# deploy_sch.net
KiCad netlist of a schematic drawn in EAGLE
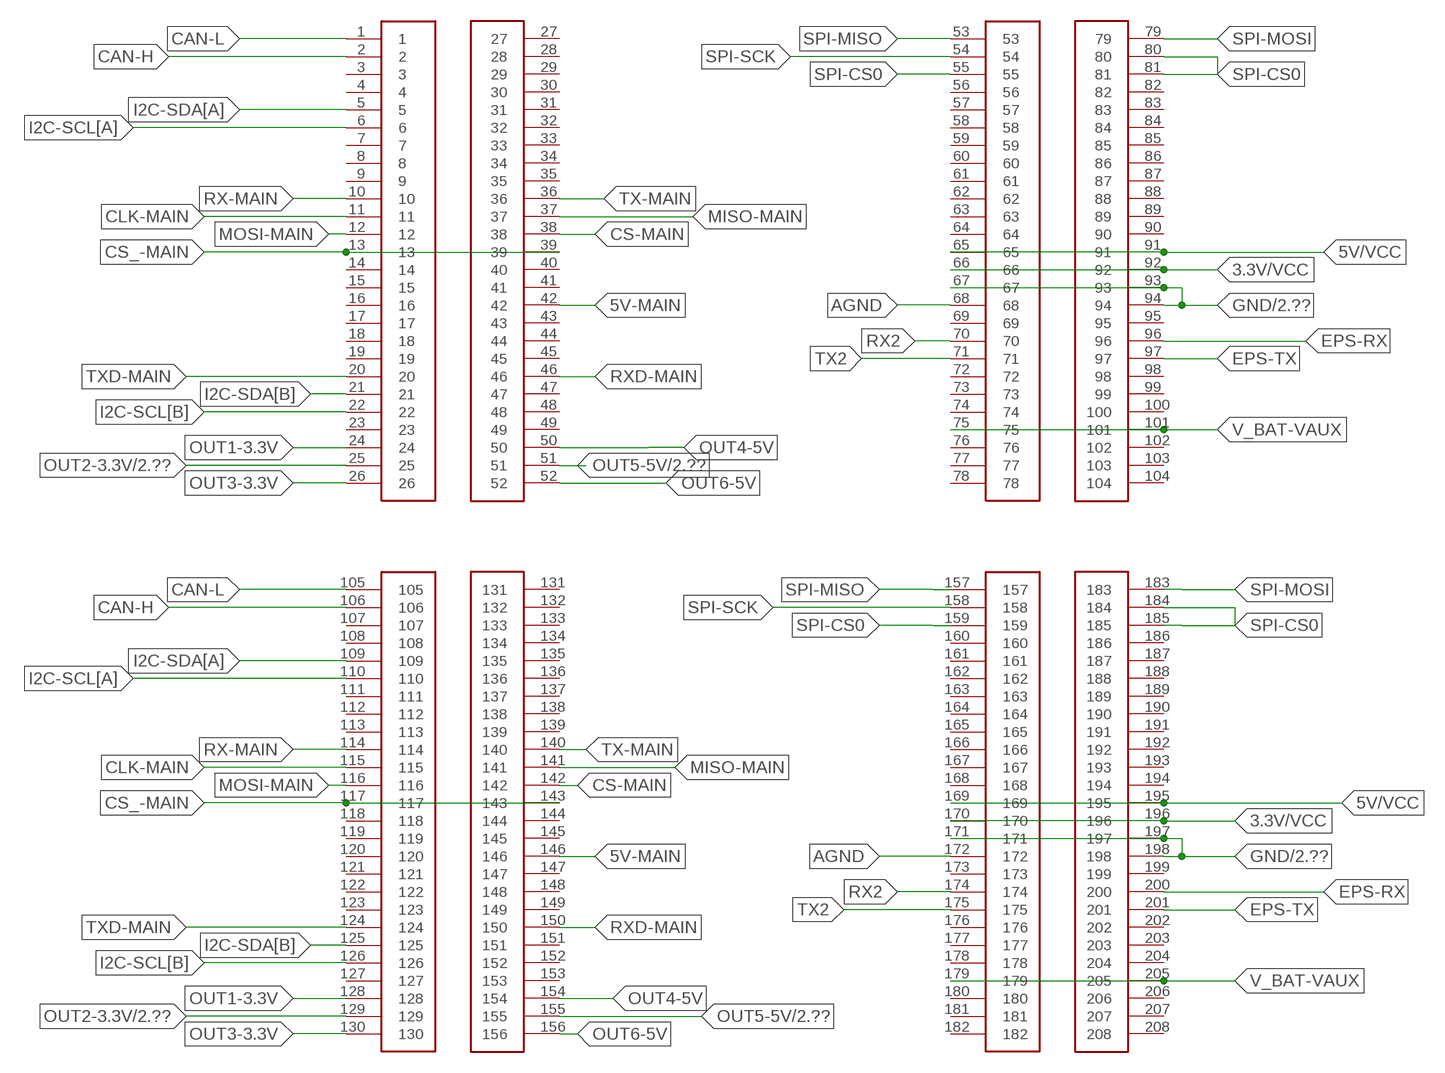
[diagram p0: schematic, sheet 1]
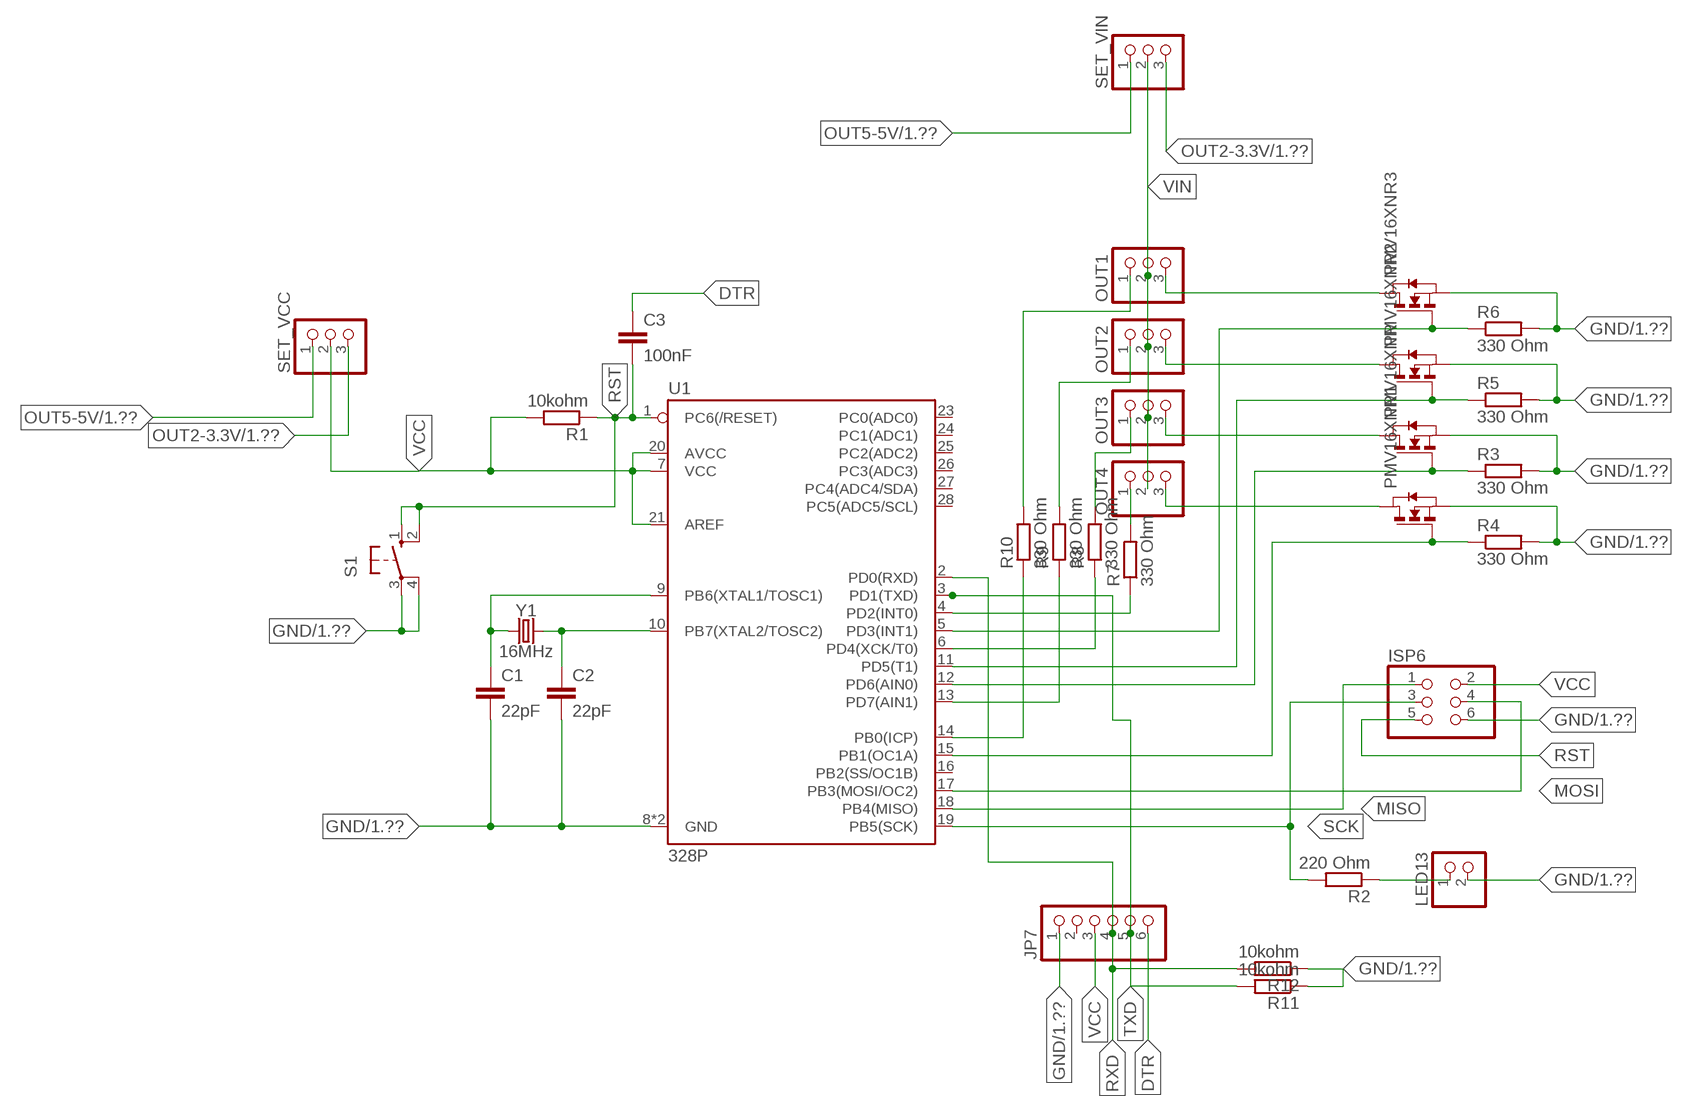
[diagram p1: schematic, sheet 2]

(export (version "E")
  (design (tool "Eeschema 10.0.6"))
  (components
    (comp (ref "C1")
      (value "22pF")
      (footprint "eagle-import:C025-025X050")
      (libsource (lib "eagle-import") (part "C-EU025-025X050"))
    )
    (comp (ref "C2")
      (value "22pF")
      (footprint "eagle-import:C025-025X050")
      (libsource (lib "eagle-import") (part "C-EU025-025X050"))
    )
    (comp (ref "C3")
      (value "100nF")
      (footprint "eagle-import:C025-025X050")
      (libsource (lib "eagle-import") (part "C-EU025-025X050"))
    )
    (comp (ref "ISP6")
      (value "PINHD-2X3")
      (footprint "eagle-import:2X03")
      (libsource (lib "eagle-import") (part "PINHD-2X3"))
    )
    (comp (ref "JP7")
      (value "PINHD-1X6")
      (footprint "eagle-import:1X06")
      (libsource (lib "eagle-import") (part "PINHD-1X6"))
    )
    (comp (ref "LED13")
      (value "PINHD-1X2")
      (footprint "eagle-import:1X02")
      (libsource (lib "eagle-import") (part "PINHD-1X2"))
    )
    (comp (ref "OUT1")
      (value "PINHD-1X3")
      (footprint "eagle-import:1X03")
      (libsource (lib "eagle-import") (part "PINHD-1X3"))
    )
    (comp (ref "OUT2")
      (value "PINHD-1X3")
      (footprint "eagle-import:1X03")
      (libsource (lib "eagle-import") (part "PINHD-1X3"))
    )
    (comp (ref "OUT3")
      (value "PINHD-1X3")
      (footprint "eagle-import:1X03")
      (libsource (lib "eagle-import") (part "PINHD-1X3"))
    )
    (comp (ref "OUT4")
      (value "PINHD-1X3")
      (footprint "eagle-import:1X03")
      (libsource (lib "eagle-import") (part "PINHD-1X3"))
    )
    (comp (ref "PMV16XNR")
      (value "NMOSSOT23")
      (footprint "eagle-import:SOT-23")
      (libsource (lib "eagle-import") (part "NMOSSOT23"))
    )
    (comp (ref "PMV16XNR1")
      (value "NMOSSOT23")
      (footprint "eagle-import:SOT-23")
      (libsource (lib "eagle-import") (part "NMOSSOT23"))
    )
    (comp (ref "PMV16XNR2")
      (value "NMOSSOT23")
      (footprint "eagle-import:SOT-23")
      (libsource (lib "eagle-import") (part "NMOSSOT23"))
    )
    (comp (ref "PMV16XNR3")
      (value "NMOSSOT23")
      (footprint "eagle-import:SOT-23")
      (libsource (lib "eagle-import") (part "NMOSSOT23"))
    )
    (comp (ref "R1")
      (value "10kohm")
      (footprint "eagle-import:0204_7")
      (libsource (lib "eagle-import") (part "R-EU_0204/7"))
    )
    (comp (ref "R2")
      (value "220 Ohm")
      (footprint "eagle-import:0204_7")
      (libsource (lib "eagle-import") (part "R-EU_0204/7"))
    )
    (comp (ref "R3")
      (value "330 Ohm")
      (footprint "eagle-import:0204_7")
      (libsource (lib "eagle-import") (part "R-EU_0204/7"))
    )
    (comp (ref "R4")
      (value "330 Ohm")
      (footprint "eagle-import:0204_7")
      (libsource (lib "eagle-import") (part "R-EU_0204/7"))
    )
    (comp (ref "R5")
      (value "330 Ohm")
      (footprint "eagle-import:0204_7")
      (libsource (lib "eagle-import") (part "R-EU_0204/7"))
    )
    (comp (ref "R6")
      (value "330 Ohm")
      (footprint "eagle-import:0204_7")
      (libsource (lib "eagle-import") (part "R-EU_0204/7"))
    )
    (comp (ref "R7")
      (value "330 Ohm")
      (footprint "eagle-import:0204_7")
      (libsource (lib "eagle-import") (part "R-EU_0204/7"))
    )
    (comp (ref "R8")
      (value "330 Ohm")
      (footprint "eagle-import:0204_7")
      (libsource (lib "eagle-import") (part "R-EU_0204/7"))
    )
    (comp (ref "R9")
      (value "330 Ohm")
      (footprint "eagle-import:0204_7")
      (libsource (lib "eagle-import") (part "R-EU_0204/7"))
    )
    (comp (ref "R10")
      (value "330 Ohm")
      (footprint "eagle-import:0204_7")
      (libsource (lib "eagle-import") (part "R-EU_0204/7"))
    )
    (comp (ref "R11")
      (value "10kohm")
      (footprint "eagle-import:0204_7")
      (libsource (lib "eagle-import") (part "R-EU_0204/7"))
    )
    (comp (ref "R12")
      (value "10kohm")
      (footprint "eagle-import:0204_7")
      (libsource (lib "eagle-import") (part "R-EU_0204/7"))
    )
    (comp (ref "S1")
      (value "10-XX")
      (footprint "eagle-import:B3F-10XX")
      (fields (field (name "MPN") "B3F-1000"))
      (libsource (lib "eagle-import") (part "10-XX"))
    )
    (comp (ref "SET_VCC")
      (value "PINHD-1X3")
      (footprint "eagle-import:1X03")
      (libsource (lib "eagle-import") (part "PINHD-1X3"))
    )
    (comp (ref "SET_VIN")
      (value "PINHD-1X3")
      (footprint "eagle-import:1X03")
      (libsource (lib "eagle-import") (part "PINHD-1X3"))
    )
    (comp (ref "U1")
      (value "328P")
      (footprint "eagle-import:DIP28")
      (libsource (lib "eagle-import") (part "ATMEGA328P_PDIP"))
    )
    (comp (ref "Y1")
      (value "16MHz")
      (footprint "eagle-import:HC49US")
      (libsource (lib "eagle-import") (part "CRYSTAL-16MHZPTH-HC49US"))
    )
    (comp (ref "U$1")
      (value "SUCHAI_STACKBREAKOUT")
      (footprint "eagle-import:SUCHAI_STACKBREAKOUT")
      (libsource (lib "eagle-import") (part "SUCHAI_STACKBREAKOUT"))
    )
  )
  (nets
    (net (code "1") (name "3.3V{slash}VCC") (class "Default")
      (node (ref "U$1") (pin "170") (pinfunction "170_170") (pintype "bidirectional"))
      (node (ref "U$1") (pin "196") (pinfunction "196_196") (pintype "bidirectional"))
      (node (ref "U$1") (pin "66") (pinfunction "66_66") (pintype "bidirectional"))
      (node (ref "U$1") (pin "92") (pinfunction "92_92") (pintype "bidirectional"))
    )
    (net (code "2") (name "5V-MAIN") (class "Default")
      (node (ref "U$1") (pin "146") (pinfunction "146_146") (pintype "bidirectional"))
      (node (ref "U$1") (pin "42") (pinfunction "42_42") (pintype "bidirectional"))
    )
    (net (code "3") (name "5V{slash}VCC") (class "Default")
      (node (ref "U$1") (pin "169") (pinfunction "169_169") (pintype "bidirectional"))
      (node (ref "U$1") (pin "195") (pinfunction "195_195") (pintype "bidirectional"))
      (node (ref "U$1") (pin "65") (pinfunction "65_65") (pintype "bidirectional"))
      (node (ref "U$1") (pin "91") (pinfunction "91_91") (pintype "bidirectional"))
    )
    (net (code "4") (name "AGND") (class "Default")
      (node (ref "U$1") (pin "172") (pinfunction "172_172") (pintype "bidirectional"))
      (node (ref "U$1") (pin "68") (pinfunction "68_68") (pintype "bidirectional"))
    )
    (net (code "5") (name "CAN-H") (class "Default")
      (node (ref "U$1") (pin "106") (pinfunction "106_106") (pintype "bidirectional"))
      (node (ref "U$1") (pin "2") (pinfunction "2_2") (pintype "bidirectional"))
    )
    (net (code "6") (name "CAN-L") (class "Default")
      (node (ref "U$1") (pin "1") (pinfunction "1_1") (pintype "bidirectional"))
      (node (ref "U$1") (pin "105") (pinfunction "105_105") (pintype "bidirectional"))
    )
    (net (code "7") (name "CLK-MAIN") (class "Default")
      (node (ref "U$1") (pin "11") (pinfunction "11_11") (pintype "bidirectional"))
      (node (ref "U$1") (pin "115") (pinfunction "115_115") (pintype "bidirectional"))
    )
    (net (code "8") (name "CS-MAIN") (class "Default")
      (node (ref "U$1") (pin "142") (pinfunction "142_142") (pintype "bidirectional"))
      (node (ref "U$1") (pin "38") (pinfunction "38_38") (pintype "bidirectional"))
    )
    (net (code "9") (name "CS_-MAIN") (class "Default")
      (node (ref "U$1") (pin "117") (pinfunction "117_117") (pintype "bidirectional"))
      (node (ref "U$1") (pin "13") (pinfunction "13_13") (pintype "bidirectional"))
      (node (ref "U$1") (pin "143") (pinfunction "143_143") (pintype "bidirectional"))
      (node (ref "U$1") (pin "39") (pinfunction "39_39") (pintype "bidirectional"))
    )
    (net (code "10") (name "DTR") (class "Default")
      (node (ref "C3") (pin "1") (pinfunction "1_1") (pintype "passive"))
      (node (ref "JP7") (pin "6") (pinfunction "6_6") (pintype "passive"))
    )
    (net (code "11") (name "EPS-RX") (class "Default")
      (node (ref "U$1") (pin "200") (pinfunction "200_200") (pintype "bidirectional"))
      (node (ref "U$1") (pin "96") (pinfunction "96_96") (pintype "bidirectional"))
    )
    (net (code "12") (name "EPS-TX") (class "Default")
      (node (ref "U$1") (pin "201") (pinfunction "201_201") (pintype "bidirectional"))
      (node (ref "U$1") (pin "97") (pinfunction "97_97") (pintype "bidirectional"))
    )
    (net (code "13") (name "GND") (class "Default")
      (node (ref "C1") (pin "2") (pinfunction "2_2") (pintype "passive"))
      (node (ref "C2") (pin "2") (pinfunction "2_2") (pintype "passive"))
      (node (ref "ISP6") (pin "6") (pinfunction "6_6") (pintype "passive"))
      (node (ref "JP7") (pin "1") (pinfunction "1_1") (pintype "passive"))
      (node (ref "LED13") (pin "2") (pinfunction "2_2") (pintype "passive"))
      (node (ref "PMV16XNR") (pin "2") (pinfunction "S_2") (pintype "passive"))
      (node (ref "PMV16XNR1") (pin "2") (pinfunction "S_2") (pintype "passive"))
      (node (ref "PMV16XNR2") (pin "2") (pinfunction "S_2") (pintype "passive"))
      (node (ref "PMV16XNR3") (pin "2") (pinfunction "S_2") (pintype "passive"))
      (node (ref "R11") (pin "1") (pinfunction "1_1") (pintype "passive"))
      (node (ref "R12") (pin "1") (pinfunction "1_1") (pintype "passive"))
      (node (ref "R3") (pin "2") (pinfunction "2_2") (pintype "passive"))
      (node (ref "R4") (pin "2") (pinfunction "2_2") (pintype "passive"))
      (node (ref "R5") (pin "2") (pinfunction "2_2") (pintype "passive"))
      (node (ref "R6") (pin "2") (pinfunction "2_2") (pintype "passive"))
      (node (ref "S1") (pin "3") (pinfunction "P_3") (pintype "passive"))
      (node (ref "S1") (pin "4") (pinfunction "P1_4") (pintype "passive"))
      (node (ref "U$1") (pin "171") (pinfunction "171_171") (pintype "bidirectional"))
      (node (ref "U$1") (pin "197") (pinfunction "197_197") (pintype "bidirectional"))
      (node (ref "U$1") (pin "198") (pinfunction "198_198") (pintype "bidirectional"))
      (node (ref "U$1") (pin "67") (pinfunction "67_67") (pintype "bidirectional"))
      (node (ref "U$1") (pin "93") (pinfunction "93_93") (pintype "bidirectional"))
      (node (ref "U$1") (pin "94") (pinfunction "94_94") (pintype "bidirectional"))
      (node (ref "U1") (pin "22") (pinfunction "GND_22") (pintype "bidirectional"))
      (node (ref "U1") (pin "8") (pinfunction "GND_8") (pintype "bidirectional"))
    )
    (net (code "14") (name "I2C-SCL[A]") (class "Default")
      (node (ref "U$1") (pin "110") (pinfunction "110_110") (pintype "bidirectional"))
      (node (ref "U$1") (pin "6") (pinfunction "6_6") (pintype "bidirectional"))
    )
    (net (code "15") (name "I2C-SCL[B]") (class "Default")
      (node (ref "U$1") (pin "126") (pinfunction "126_126") (pintype "bidirectional"))
      (node (ref "U$1") (pin "22") (pinfunction "22_22") (pintype "bidirectional"))
    )
    (net (code "16") (name "I2C-SDA[A]") (class "Default")
      (node (ref "U$1") (pin "109") (pinfunction "109_109") (pintype "bidirectional"))
      (node (ref "U$1") (pin "5") (pinfunction "5_5") (pintype "bidirectional"))
    )
    (net (code "17") (name "I2C-SDA[B]") (class "Default")
      (node (ref "U$1") (pin "125") (pinfunction "125_125") (pintype "bidirectional"))
      (node (ref "U$1") (pin "21") (pinfunction "21_21") (pintype "bidirectional"))
    )
    (net (code "18") (name "MISO") (class "Default")
      (node (ref "ISP6") (pin "1") (pinfunction "1_1") (pintype "passive"))
      (node (ref "U1") (pin "18") (pinfunction "PB4(MISO)_18") (pintype "bidirectional"))
    )
    (net (code "19") (name "MISO-MAIN") (class "Default")
      (node (ref "U$1") (pin "141") (pinfunction "141_141") (pintype "bidirectional"))
      (node (ref "U$1") (pin "37") (pinfunction "37_37") (pintype "bidirectional"))
    )
    (net (code "20") (name "MOSI") (class "Default")
      (node (ref "ISP6") (pin "4") (pinfunction "4_4") (pintype "passive"))
      (node (ref "U1") (pin "17") (pinfunction "PB3(MOSI/OC2)_17") (pintype "bidirectional"))
    )
    (net (code "21") (name "MOSI-MAIN") (class "Default")
      (node (ref "U$1") (pin "116") (pinfunction "116_116") (pintype "bidirectional"))
      (node (ref "U$1") (pin "12") (pinfunction "12_12") (pintype "bidirectional"))
    )
    (net (code "22") (name "Net-(LED13-Pad1)") (class "Default")
      (node (ref "LED13") (pin "1") (pinfunction "1_1") (pintype "passive"))
      (node (ref "R2") (pin "1") (pinfunction "1_1") (pintype "passive"))
    )
    (net (code "23") (name "Net-(OUT1-Pad1)") (class "Default")
      (node (ref "OUT1") (pin "1") (pinfunction "1_1") (pintype "passive"))
      (node (ref "R10") (pin "2") (pinfunction "2_2") (pintype "passive"))
    )
    (net (code "24") (name "Net-(OUT2-Pad1)") (class "Default")
      (node (ref "OUT2") (pin "1") (pinfunction "1_1") (pintype "passive"))
      (node (ref "R9") (pin "2") (pinfunction "2_2") (pintype "passive"))
    )
    (net (code "25") (name "Net-(OUT3-Pad1)") (class "Default")
      (node (ref "OUT3") (pin "1") (pinfunction "1_1") (pintype "passive"))
      (node (ref "R8") (pin "2") (pinfunction "2_2") (pintype "passive"))
    )
    (net (code "26") (name "Net-(OUT4-Pad1)") (class "Default")
      (node (ref "OUT4") (pin "1") (pinfunction "1_1") (pintype "passive"))
      (node (ref "R7") (pin "2") (pinfunction "2_2") (pintype "passive"))
    )
    (net (code "27") (name "Net-(PMV16XNR-D)") (class "Default")
      (node (ref "OUT3") (pin "3") (pinfunction "3_3") (pintype "passive"))
      (node (ref "PMV16XNR") (pin "1") (pinfunction "D_1") (pintype "passive"))
    )
    (net (code "28") (name "Net-(PMV16XNR-G)") (class "Default")
      (node (ref "PMV16XNR") (pin "3") (pinfunction "G_3") (pintype "passive"))
      (node (ref "R3") (pin "1") (pinfunction "1_1") (pintype "passive"))
      (node (ref "U1") (pin "12") (pinfunction "PD6(AIN0)_12") (pintype "bidirectional"))
    )
    (net (code "29") (name "Net-(PMV16XNR1-D)") (class "Default")
      (node (ref "OUT4") (pin "3") (pinfunction "3_3") (pintype "passive"))
      (node (ref "PMV16XNR1") (pin "1") (pinfunction "D_1") (pintype "passive"))
    )
    (net (code "30") (name "Net-(PMV16XNR1-G)") (class "Default")
      (node (ref "PMV16XNR1") (pin "3") (pinfunction "G_3") (pintype "passive"))
      (node (ref "R4") (pin "1") (pinfunction "1_1") (pintype "passive"))
      (node (ref "U1") (pin "15") (pinfunction "PB1(OC1A)_15") (pintype "bidirectional"))
    )
    (net (code "31") (name "Net-(PMV16XNR2-D)") (class "Default")
      (node (ref "OUT2") (pin "3") (pinfunction "3_3") (pintype "passive"))
      (node (ref "PMV16XNR2") (pin "1") (pinfunction "D_1") (pintype "passive"))
    )
    (net (code "32") (name "Net-(PMV16XNR2-G)") (class "Default")
      (node (ref "PMV16XNR2") (pin "3") (pinfunction "G_3") (pintype "passive"))
      (node (ref "R5") (pin "1") (pinfunction "1_1") (pintype "passive"))
      (node (ref "U1") (pin "11") (pinfunction "PD5(T1)_11") (pintype "bidirectional"))
    )
    (net (code "33") (name "Net-(PMV16XNR3-D)") (class "Default")
      (node (ref "OUT1") (pin "3") (pinfunction "3_3") (pintype "passive"))
      (node (ref "PMV16XNR3") (pin "1") (pinfunction "D_1") (pintype "passive"))
    )
    (net (code "34") (name "Net-(PMV16XNR3-G)") (class "Default")
      (node (ref "PMV16XNR3") (pin "3") (pinfunction "G_3") (pintype "passive"))
      (node (ref "R6") (pin "1") (pinfunction "1_1") (pintype "passive"))
      (node (ref "U1") (pin "5") (pinfunction "PD3(INT1)_5") (pintype "bidirectional"))
    )
    (net (code "35") (name "Net-(U1-PB0(ICP))") (class "Default")
      (node (ref "R10") (pin "1") (pinfunction "1_1") (pintype "passive"))
      (node (ref "U1") (pin "14") (pinfunction "PB0(ICP)_14") (pintype "bidirectional"))
    )
    (net (code "36") (name "Net-(U1-PB6(XTAL1{slash}TOSC1))") (class "Default")
      (node (ref "C1") (pin "1") (pinfunction "1_1") (pintype "passive"))
      (node (ref "U1") (pin "9") (pinfunction "PB6(XTAL1/TOSC1)_9") (pintype "bidirectional"))
      (node (ref "Y1") (pin "1") (pinfunction "1_1") (pintype "passive"))
    )
    (net (code "37") (name "Net-(U1-PB7(XTAL2{slash}TOSC2))") (class "Default")
      (node (ref "C2") (pin "1") (pinfunction "1_1") (pintype "passive"))
      (node (ref "U1") (pin "10") (pinfunction "PB7(XTAL2/TOSC2)_10") (pintype "bidirectional"))
      (node (ref "Y1") (pin "2") (pinfunction "2_2") (pintype "passive"))
    )
    (net (code "38") (name "Net-(U1-PD2(INT0))") (class "Default")
      (node (ref "R7") (pin "1") (pinfunction "1_1") (pintype "passive"))
      (node (ref "U1") (pin "4") (pinfunction "PD2(INT0)_4") (pintype "bidirectional"))
    )
    (net (code "39") (name "Net-(U1-PD4(XCK{slash}T0))") (class "Default")
      (node (ref "R8") (pin "1") (pinfunction "1_1") (pintype "passive"))
      (node (ref "U1") (pin "6") (pinfunction "PD4(XCK/T0)_6") (pintype "bidirectional"))
    )
    (net (code "40") (name "Net-(U1-PD7(AIN1))") (class "Default")
      (node (ref "R9") (pin "1") (pinfunction "1_1") (pintype "passive"))
      (node (ref "U1") (pin "13") (pinfunction "PD7(AIN1)_13") (pintype "bidirectional"))
    )
    (net (code "41") (name "OUT1-3.3V") (class "Default")
      (node (ref "U$1") (pin "128") (pinfunction "128_128") (pintype "bidirectional"))
      (node (ref "U$1") (pin "24") (pinfunction "24_24") (pintype "bidirectional"))
    )
    (net (code "42") (name "OUT2-3.3V") (class "Default")
      (node (ref "SET_VCC") (pin "3") (pinfunction "3_3") (pintype "passive"))
      (node (ref "SET_VIN") (pin "3") (pinfunction "3_3") (pintype "passive"))
      (node (ref "U$1") (pin "129") (pinfunction "129_129") (pintype "bidirectional"))
      (node (ref "U$1") (pin "25") (pinfunction "25_25") (pintype "bidirectional"))
    )
    (net (code "43") (name "OUT3-3.3V") (class "Default")
      (node (ref "U$1") (pin "130") (pinfunction "130_130") (pintype "bidirectional"))
      (node (ref "U$1") (pin "26") (pinfunction "26_26") (pintype "bidirectional"))
    )
    (net (code "44") (name "OUT4-5V") (class "Default")
      (node (ref "U$1") (pin "154") (pinfunction "154_154") (pintype "bidirectional"))
      (node (ref "U$1") (pin "50") (pinfunction "50_50") (pintype "bidirectional"))
    )
    (net (code "45") (name "OUT5-5V") (class "Default")
      (node (ref "SET_VCC") (pin "1") (pinfunction "1_1") (pintype "passive"))
      (node (ref "SET_VIN") (pin "1") (pinfunction "1_1") (pintype "passive"))
      (node (ref "U$1") (pin "155") (pinfunction "155_155") (pintype "bidirectional"))
      (node (ref "U$1") (pin "51") (pinfunction "51_51") (pintype "bidirectional"))
    )
    (net (code "46") (name "OUT6-5V") (class "Default")
      (node (ref "U$1") (pin "156") (pinfunction "156_156") (pintype "bidirectional"))
      (node (ref "U$1") (pin "52") (pinfunction "52_52") (pintype "bidirectional"))
    )
    (net (code "47") (name "RST") (class "Default")
      (node (ref "C3") (pin "2") (pinfunction "2_2") (pintype "passive"))
      (node (ref "ISP6") (pin "5") (pinfunction "5_5") (pintype "passive"))
      (node (ref "R1") (pin "1") (pinfunction "1_1") (pintype "passive"))
      (node (ref "S1") (pin "1") (pinfunction "S_1") (pintype "passive"))
      (node (ref "S1") (pin "2") (pinfunction "S1_2") (pintype "passive"))
      (node (ref "U1") (pin "1") (pinfunction "PC6(/RESET)_1") (pintype "bidirectional"))
    )
    (net (code "48") (name "RX-MAIN") (class "Default")
      (node (ref "U$1") (pin "10") (pinfunction "10_10") (pintype "bidirectional"))
      (node (ref "U$1") (pin "114") (pinfunction "114_114") (pintype "bidirectional"))
    )
    (net (code "49") (name "RX2") (class "Default")
      (node (ref "U$1") (pin "174") (pinfunction "174_174") (pintype "bidirectional"))
      (node (ref "U$1") (pin "70") (pinfunction "70_70") (pintype "bidirectional"))
    )
    (net (code "50") (name "RXD") (class "Default")
      (node (ref "JP7") (pin "4") (pinfunction "4_4") (pintype "passive"))
      (node (ref "R12") (pin "2") (pinfunction "2_2") (pintype "passive"))
      (node (ref "U1") (pin "2") (pinfunction "PD0(RXD)_2") (pintype "bidirectional"))
    )
    (net (code "51") (name "RXD-MAIN") (class "Default")
      (node (ref "U$1") (pin "150") (pinfunction "150_150") (pintype "bidirectional"))
      (node (ref "U$1") (pin "46") (pinfunction "46_46") (pintype "bidirectional"))
    )
    (net (code "52") (name "SCK") (class "Default")
      (node (ref "ISP6") (pin "3") (pinfunction "3_3") (pintype "passive"))
      (node (ref "R2") (pin "2") (pinfunction "2_2") (pintype "passive"))
      (node (ref "U1") (pin "19") (pinfunction "PB5(SCK)_19") (pintype "bidirectional"))
    )
    (net (code "53") (name "SPI-CS0") (class "Default")
      (node (ref "U$1") (pin "159") (pinfunction "159_159") (pintype "bidirectional"))
      (node (ref "U$1") (pin "184") (pinfunction "184_184") (pintype "bidirectional"))
      (node (ref "U$1") (pin "185") (pinfunction "185_185") (pintype "bidirectional"))
      (node (ref "U$1") (pin "55") (pinfunction "55_55") (pintype "bidirectional"))
      (node (ref "U$1") (pin "80") (pinfunction "80_80") (pintype "bidirectional"))
      (node (ref "U$1") (pin "81") (pinfunction "81_81") (pintype "bidirectional"))
    )
    (net (code "54") (name "SPI-MISO") (class "Default")
      (node (ref "U$1") (pin "157") (pinfunction "157_157") (pintype "bidirectional"))
      (node (ref "U$1") (pin "53") (pinfunction "53_53") (pintype "bidirectional"))
    )
    (net (code "55") (name "SPI-MOSI") (class "Default")
      (node (ref "U$1") (pin "183") (pinfunction "183_183") (pintype "bidirectional"))
      (node (ref "U$1") (pin "79") (pinfunction "79_79") (pintype "bidirectional"))
    )
    (net (code "56") (name "SPI-SCK") (class "Default")
      (node (ref "U$1") (pin "158") (pinfunction "158_158") (pintype "bidirectional"))
      (node (ref "U$1") (pin "54") (pinfunction "54_54") (pintype "bidirectional"))
    )
    (net (code "57") (name "TX-MAIN") (class "Default")
      (node (ref "U$1") (pin "140") (pinfunction "140_140") (pintype "bidirectional"))
      (node (ref "U$1") (pin "36") (pinfunction "36_36") (pintype "bidirectional"))
    )
    (net (code "58") (name "TX2") (class "Default")
      (node (ref "U$1") (pin "175") (pinfunction "175_175") (pintype "bidirectional"))
      (node (ref "U$1") (pin "71") (pinfunction "71_71") (pintype "bidirectional"))
    )
    (net (code "59") (name "TXD") (class "Default")
      (node (ref "JP7") (pin "5") (pinfunction "5_5") (pintype "passive"))
      (node (ref "R11") (pin "2") (pinfunction "2_2") (pintype "passive"))
      (node (ref "U1") (pin "3") (pinfunction "PD1(TXD)_3") (pintype "bidirectional"))
    )
    (net (code "60") (name "TXD-MAIN") (class "Default")
      (node (ref "U$1") (pin "124") (pinfunction "124_124") (pintype "bidirectional"))
      (node (ref "U$1") (pin "20") (pinfunction "20_20") (pintype "bidirectional"))
    )
    (net (code "61") (name "VCC") (class "Default")
      (node (ref "ISP6") (pin "2") (pinfunction "2_2") (pintype "passive"))
      (node (ref "JP7") (pin "3") (pinfunction "3_3") (pintype "passive"))
      (node (ref "R1") (pin "2") (pinfunction "2_2") (pintype "passive"))
      (node (ref "SET_VCC") (pin "2") (pinfunction "2_2") (pintype "passive"))
      (node (ref "U1") (pin "20") (pinfunction "AVCC_20") (pintype "bidirectional"))
      (node (ref "U1") (pin "21") (pinfunction "AREF_21") (pintype "bidirectional"))
      (node (ref "U1") (pin "7") (pinfunction "VCC_7") (pintype "bidirectional"))
    )
    (net (code "62") (name "VIN") (class "Default")
      (node (ref "OUT1") (pin "2") (pinfunction "2_2") (pintype "passive"))
      (node (ref "OUT2") (pin "2") (pinfunction "2_2") (pintype "passive"))
      (node (ref "OUT3") (pin "2") (pinfunction "2_2") (pintype "passive"))
      (node (ref "OUT4") (pin "2") (pinfunction "2_2") (pintype "passive"))
      (node (ref "SET_VIN") (pin "2") (pinfunction "2_2") (pintype "passive"))
    )
    (net (code "63") (name "V_BAT-VAUX") (class "Default")
      (node (ref "U$1") (pin "101") (pinfunction "101_101") (pintype "bidirectional"))
      (node (ref "U$1") (pin "179") (pinfunction "179_179") (pintype "bidirectional"))
      (node (ref "U$1") (pin "205") (pinfunction "205_205") (pintype "bidirectional"))
      (node (ref "U$1") (pin "75") (pinfunction "75_75") (pintype "bidirectional"))
    )
    (net (code "64") (name "unconnected-(JP7-Pad2)") (class "Default")
      (node (ref "JP7") (pin "2") (pinfunction "2_2") (pintype "passive"))
    )
    (net (code "65") (name "unconnected-(U$1-Pad3)") (class "Default")
      (node (ref "U$1") (pin "3") (pinfunction "3_3") (pintype "bidirectional"))
    )
    (net (code "66") (name "unconnected-(U$1-Pad4)") (class "Default")
      (node (ref "U$1") (pin "4") (pinfunction "4_4") (pintype "bidirectional"))
    )
    (net (code "67") (name "unconnected-(U$1-Pad7)") (class "Default")
      (node (ref "U$1") (pin "7") (pinfunction "7_7") (pintype "bidirectional"))
    )
    (net (code "68") (name "unconnected-(U$1-Pad8)") (class "Default")
      (node (ref "U$1") (pin "8") (pinfunction "8_8") (pintype "bidirectional"))
    )
    (net (code "69") (name "unconnected-(U$1-Pad9)") (class "Default")
      (node (ref "U$1") (pin "9") (pinfunction "9_9") (pintype "bidirectional"))
    )
    (net (code "70") (name "unconnected-(U$1-Pad14)") (class "Default")
      (node (ref "U$1") (pin "14") (pinfunction "14_14") (pintype "bidirectional"))
    )
    (net (code "71") (name "unconnected-(U$1-Pad15)") (class "Default")
      (node (ref "U$1") (pin "15") (pinfunction "15_15") (pintype "bidirectional"))
    )
    (net (code "72") (name "unconnected-(U$1-Pad16)") (class "Default")
      (node (ref "U$1") (pin "16") (pinfunction "16_16") (pintype "bidirectional"))
    )
    (net (code "73") (name "unconnected-(U$1-Pad17)") (class "Default")
      (node (ref "U$1") (pin "17") (pinfunction "17_17") (pintype "bidirectional"))
    )
    (net (code "74") (name "unconnected-(U$1-Pad18)") (class "Default")
      (node (ref "U$1") (pin "18") (pinfunction "18_18") (pintype "bidirectional"))
    )
    (net (code "75") (name "unconnected-(U$1-Pad19)") (class "Default")
      (node (ref "U$1") (pin "19") (pinfunction "19_19") (pintype "bidirectional"))
    )
    (net (code "76") (name "unconnected-(U$1-Pad23)") (class "Default")
      (node (ref "U$1") (pin "23") (pinfunction "23_23") (pintype "bidirectional"))
    )
    (net (code "77") (name "unconnected-(U$1-Pad27)") (class "Default")
      (node (ref "U$1") (pin "27") (pinfunction "27_27") (pintype "bidirectional"))
    )
    (net (code "78") (name "unconnected-(U$1-Pad28)") (class "Default")
      (node (ref "U$1") (pin "28") (pinfunction "28_28") (pintype "bidirectional"))
    )
    (net (code "79") (name "unconnected-(U$1-Pad29)") (class "Default")
      (node (ref "U$1") (pin "29") (pinfunction "29_29") (pintype "bidirectional"))
    )
    (net (code "80") (name "unconnected-(U$1-Pad30)") (class "Default")
      (node (ref "U$1") (pin "30") (pinfunction "30_30") (pintype "bidirectional"))
    )
    (net (code "81") (name "unconnected-(U$1-Pad31)") (class "Default")
      (node (ref "U$1") (pin "31") (pinfunction "31_31") (pintype "bidirectional"))
    )
    (net (code "82") (name "unconnected-(U$1-Pad32)") (class "Default")
      (node (ref "U$1") (pin "32") (pinfunction "32_32") (pintype "bidirectional"))
    )
    (net (code "83") (name "unconnected-(U$1-Pad33)") (class "Default")
      (node (ref "U$1") (pin "33") (pinfunction "33_33") (pintype "bidirectional"))
    )
    (net (code "84") (name "unconnected-(U$1-Pad34)") (class "Default")
      (node (ref "U$1") (pin "34") (pinfunction "34_34") (pintype "bidirectional"))
    )
    (net (code "85") (name "unconnected-(U$1-Pad35)") (class "Default")
      (node (ref "U$1") (pin "35") (pinfunction "35_35") (pintype "bidirectional"))
    )
    (net (code "86") (name "unconnected-(U$1-Pad40)") (class "Default")
      (node (ref "U$1") (pin "40") (pinfunction "40_40") (pintype "bidirectional"))
    )
    (net (code "87") (name "unconnected-(U$1-Pad41)") (class "Default")
      (node (ref "U$1") (pin "41") (pinfunction "41_41") (pintype "bidirectional"))
    )
    (net (code "88") (name "unconnected-(U$1-Pad43)") (class "Default")
      (node (ref "U$1") (pin "43") (pinfunction "43_43") (pintype "bidirectional"))
    )
    (net (code "89") (name "unconnected-(U$1-Pad44)") (class "Default")
      (node (ref "U$1") (pin "44") (pinfunction "44_44") (pintype "bidirectional"))
    )
    (net (code "90") (name "unconnected-(U$1-Pad45)") (class "Default")
      (node (ref "U$1") (pin "45") (pinfunction "45_45") (pintype "bidirectional"))
    )
    (net (code "91") (name "unconnected-(U$1-Pad47)") (class "Default")
      (node (ref "U$1") (pin "47") (pinfunction "47_47") (pintype "bidirectional"))
    )
    (net (code "92") (name "unconnected-(U$1-Pad48)") (class "Default")
      (node (ref "U$1") (pin "48") (pinfunction "48_48") (pintype "bidirectional"))
    )
    (net (code "93") (name "unconnected-(U$1-Pad49)") (class "Default")
      (node (ref "U$1") (pin "49") (pinfunction "49_49") (pintype "bidirectional"))
    )
    (net (code "94") (name "unconnected-(U$1-Pad56)") (class "Default")
      (node (ref "U$1") (pin "56") (pinfunction "56_56") (pintype "bidirectional"))
    )
    (net (code "95") (name "unconnected-(U$1-Pad57)") (class "Default")
      (node (ref "U$1") (pin "57") (pinfunction "57_57") (pintype "bidirectional"))
    )
    (net (code "96") (name "unconnected-(U$1-Pad58)") (class "Default")
      (node (ref "U$1") (pin "58") (pinfunction "58_58") (pintype "bidirectional"))
    )
    (net (code "97") (name "unconnected-(U$1-Pad59)") (class "Default")
      (node (ref "U$1") (pin "59") (pinfunction "59_59") (pintype "bidirectional"))
    )
    (net (code "98") (name "unconnected-(U$1-Pad60)") (class "Default")
      (node (ref "U$1") (pin "60") (pinfunction "60_60") (pintype "bidirectional"))
    )
    (net (code "99") (name "unconnected-(U$1-Pad61)") (class "Default")
      (node (ref "U$1") (pin "61") (pinfunction "61_61") (pintype "bidirectional"))
    )
    (net (code "100") (name "unconnected-(U$1-Pad62)") (class "Default")
      (node (ref "U$1") (pin "62") (pinfunction "62_62") (pintype "bidirectional"))
    )
    (net (code "101") (name "unconnected-(U$1-Pad63)") (class "Default")
      (node (ref "U$1") (pin "63") (pinfunction "63_63") (pintype "bidirectional"))
    )
    (net (code "102") (name "unconnected-(U$1-Pad64)") (class "Default")
      (node (ref "U$1") (pin "64") (pinfunction "64_64") (pintype "bidirectional"))
    )
    (net (code "103") (name "unconnected-(U$1-Pad69)") (class "Default")
      (node (ref "U$1") (pin "69") (pinfunction "69_69") (pintype "bidirectional"))
    )
    (net (code "104") (name "unconnected-(U$1-Pad72)") (class "Default")
      (node (ref "U$1") (pin "72") (pinfunction "72_72") (pintype "bidirectional"))
    )
    (net (code "105") (name "unconnected-(U$1-Pad73)") (class "Default")
      (node (ref "U$1") (pin "73") (pinfunction "73_73") (pintype "bidirectional"))
    )
    (net (code "106") (name "unconnected-(U$1-Pad74)") (class "Default")
      (node (ref "U$1") (pin "74") (pinfunction "74_74") (pintype "bidirectional"))
    )
    (net (code "107") (name "unconnected-(U$1-Pad76)") (class "Default")
      (node (ref "U$1") (pin "76") (pinfunction "76_76") (pintype "bidirectional"))
    )
    (net (code "108") (name "unconnected-(U$1-Pad77)") (class "Default")
      (node (ref "U$1") (pin "77") (pinfunction "77_77") (pintype "bidirectional"))
    )
    (net (code "109") (name "unconnected-(U$1-Pad78)") (class "Default")
      (node (ref "U$1") (pin "78") (pinfunction "78_78") (pintype "bidirectional"))
    )
    (net (code "110") (name "unconnected-(U$1-Pad82)") (class "Default")
      (node (ref "U$1") (pin "82") (pinfunction "82_82") (pintype "bidirectional"))
    )
    (net (code "111") (name "unconnected-(U$1-Pad83)") (class "Default")
      (node (ref "U$1") (pin "83") (pinfunction "83_83") (pintype "bidirectional"))
    )
    (net (code "112") (name "unconnected-(U$1-Pad84)") (class "Default")
      (node (ref "U$1") (pin "84") (pinfunction "84_84") (pintype "bidirectional"))
    )
    (net (code "113") (name "unconnected-(U$1-Pad85)") (class "Default")
      (node (ref "U$1") (pin "85") (pinfunction "85_85") (pintype "bidirectional"))
    )
    (net (code "114") (name "unconnected-(U$1-Pad86)") (class "Default")
      (node (ref "U$1") (pin "86") (pinfunction "86_86") (pintype "bidirectional"))
    )
    (net (code "115") (name "unconnected-(U$1-Pad87)") (class "Default")
      (node (ref "U$1") (pin "87") (pinfunction "87_87") (pintype "bidirectional"))
    )
    (net (code "116") (name "unconnected-(U$1-Pad88)") (class "Default")
      (node (ref "U$1") (pin "88") (pinfunction "88_88") (pintype "bidirectional"))
    )
    (net (code "117") (name "unconnected-(U$1-Pad89)") (class "Default")
      (node (ref "U$1") (pin "89") (pinfunction "89_89") (pintype "bidirectional"))
    )
    (net (code "118") (name "unconnected-(U$1-Pad90)") (class "Default")
      (node (ref "U$1") (pin "90") (pinfunction "90_90") (pintype "bidirectional"))
    )
    (net (code "119") (name "unconnected-(U$1-Pad95)") (class "Default")
      (node (ref "U$1") (pin "95") (pinfunction "95_95") (pintype "bidirectional"))
    )
    (net (code "120") (name "unconnected-(U$1-Pad98)") (class "Default")
      (node (ref "U$1") (pin "98") (pinfunction "98_98") (pintype "bidirectional"))
    )
    (net (code "121") (name "unconnected-(U$1-Pad99)") (class "Default")
      (node (ref "U$1") (pin "99") (pinfunction "99_99") (pintype "bidirectional"))
    )
    (net (code "122") (name "unconnected-(U$1-Pad100)") (class "Default")
      (node (ref "U$1") (pin "100") (pinfunction "100_100") (pintype "bidirectional"))
    )
    (net (code "123") (name "unconnected-(U$1-Pad102)") (class "Default")
      (node (ref "U$1") (pin "102") (pinfunction "102_102") (pintype "bidirectional"))
    )
    (net (code "124") (name "unconnected-(U$1-Pad103)") (class "Default")
      (node (ref "U$1") (pin "103") (pinfunction "103_103") (pintype "bidirectional"))
    )
    (net (code "125") (name "unconnected-(U$1-Pad104)") (class "Default")
      (node (ref "U$1") (pin "104") (pinfunction "104_104") (pintype "bidirectional"))
    )
    (net (code "126") (name "unconnected-(U$1-Pad107)") (class "Default")
      (node (ref "U$1") (pin "107") (pinfunction "107_107") (pintype "bidirectional"))
    )
    (net (code "127") (name "unconnected-(U$1-Pad108)") (class "Default")
      (node (ref "U$1") (pin "108") (pinfunction "108_108") (pintype "bidirectional"))
    )
    (net (code "128") (name "unconnected-(U$1-Pad111)") (class "Default")
      (node (ref "U$1") (pin "111") (pinfunction "111_111") (pintype "bidirectional"))
    )
    (net (code "129") (name "unconnected-(U$1-Pad112)") (class "Default")
      (node (ref "U$1") (pin "112") (pinfunction "112_112") (pintype "bidirectional"))
    )
    (net (code "130") (name "unconnected-(U$1-Pad113)") (class "Default")
      (node (ref "U$1") (pin "113") (pinfunction "113_113") (pintype "bidirectional"))
    )
    (net (code "131") (name "unconnected-(U$1-Pad118)") (class "Default")
      (node (ref "U$1") (pin "118") (pinfunction "118_118") (pintype "bidirectional"))
    )
    (net (code "132") (name "unconnected-(U$1-Pad119)") (class "Default")
      (node (ref "U$1") (pin "119") (pinfunction "119_119") (pintype "bidirectional"))
    )
    (net (code "133") (name "unconnected-(U$1-Pad120)") (class "Default")
      (node (ref "U$1") (pin "120") (pinfunction "120_120") (pintype "bidirectional"))
    )
    (net (code "134") (name "unconnected-(U$1-Pad121)") (class "Default")
      (node (ref "U$1") (pin "121") (pinfunction "121_121") (pintype "bidirectional"))
    )
    (net (code "135") (name "unconnected-(U$1-Pad122)") (class "Default")
      (node (ref "U$1") (pin "122") (pinfunction "122_122") (pintype "bidirectional"))
    )
    (net (code "136") (name "unconnected-(U$1-Pad123)") (class "Default")
      (node (ref "U$1") (pin "123") (pinfunction "123_123") (pintype "bidirectional"))
    )
    (net (code "137") (name "unconnected-(U$1-Pad127)") (class "Default")
      (node (ref "U$1") (pin "127") (pinfunction "127_127") (pintype "bidirectional"))
    )
    (net (code "138") (name "unconnected-(U$1-Pad131)") (class "Default")
      (node (ref "U$1") (pin "131") (pinfunction "131_131") (pintype "bidirectional"))
    )
    (net (code "139") (name "unconnected-(U$1-Pad132)") (class "Default")
      (node (ref "U$1") (pin "132") (pinfunction "132_132") (pintype "bidirectional"))
    )
    (net (code "140") (name "unconnected-(U$1-Pad133)") (class "Default")
      (node (ref "U$1") (pin "133") (pinfunction "133_133") (pintype "bidirectional"))
    )
    (net (code "141") (name "unconnected-(U$1-Pad134)") (class "Default")
      (node (ref "U$1") (pin "134") (pinfunction "134_134") (pintype "bidirectional"))
    )
    (net (code "142") (name "unconnected-(U$1-Pad135)") (class "Default")
      (node (ref "U$1") (pin "135") (pinfunction "135_135") (pintype "bidirectional"))
    )
    (net (code "143") (name "unconnected-(U$1-Pad136)") (class "Default")
      (node (ref "U$1") (pin "136") (pinfunction "136_136") (pintype "bidirectional"))
    )
    (net (code "144") (name "unconnected-(U$1-Pad137)") (class "Default")
      (node (ref "U$1") (pin "137") (pinfunction "137_137") (pintype "bidirectional"))
    )
    (net (code "145") (name "unconnected-(U$1-Pad138)") (class "Default")
      (node (ref "U$1") (pin "138") (pinfunction "138_138") (pintype "bidirectional"))
    )
    (net (code "146") (name "unconnected-(U$1-Pad139)") (class "Default")
      (node (ref "U$1") (pin "139") (pinfunction "139_139") (pintype "bidirectional"))
    )
    (net (code "147") (name "unconnected-(U$1-Pad144)") (class "Default")
      (node (ref "U$1") (pin "144") (pinfunction "144_144") (pintype "bidirectional"))
    )
    (net (code "148") (name "unconnected-(U$1-Pad145)") (class "Default")
      (node (ref "U$1") (pin "145") (pinfunction "145_145") (pintype "bidirectional"))
    )
    (net (code "149") (name "unconnected-(U$1-Pad147)") (class "Default")
      (node (ref "U$1") (pin "147") (pinfunction "147_147") (pintype "bidirectional"))
    )
    (net (code "150") (name "unconnected-(U$1-Pad148)") (class "Default")
      (node (ref "U$1") (pin "148") (pinfunction "148_148") (pintype "bidirectional"))
    )
    (net (code "151") (name "unconnected-(U$1-Pad149)") (class "Default")
      (node (ref "U$1") (pin "149") (pinfunction "149_149") (pintype "bidirectional"))
    )
    (net (code "152") (name "unconnected-(U$1-Pad151)") (class "Default")
      (node (ref "U$1") (pin "151") (pinfunction "151_151") (pintype "bidirectional"))
    )
    (net (code "153") (name "unconnected-(U$1-Pad152)") (class "Default")
      (node (ref "U$1") (pin "152") (pinfunction "152_152") (pintype "bidirectional"))
    )
    (net (code "154") (name "unconnected-(U$1-Pad153)") (class "Default")
      (node (ref "U$1") (pin "153") (pinfunction "153_153") (pintype "bidirectional"))
    )
    (net (code "155") (name "unconnected-(U$1-Pad160)") (class "Default")
      (node (ref "U$1") (pin "160") (pinfunction "160_160") (pintype "bidirectional"))
    )
    (net (code "156") (name "unconnected-(U$1-Pad161)") (class "Default")
      (node (ref "U$1") (pin "161") (pinfunction "161_161") (pintype "bidirectional"))
    )
    (net (code "157") (name "unconnected-(U$1-Pad162)") (class "Default")
      (node (ref "U$1") (pin "162") (pinfunction "162_162") (pintype "bidirectional"))
    )
    (net (code "158") (name "unconnected-(U$1-Pad163)") (class "Default")
      (node (ref "U$1") (pin "163") (pinfunction "163_163") (pintype "bidirectional"))
    )
    (net (code "159") (name "unconnected-(U$1-Pad164)") (class "Default")
      (node (ref "U$1") (pin "164") (pinfunction "164_164") (pintype "bidirectional"))
    )
    (net (code "160") (name "unconnected-(U$1-Pad165)") (class "Default")
      (node (ref "U$1") (pin "165") (pinfunction "165_165") (pintype "bidirectional"))
    )
    (net (code "161") (name "unconnected-(U$1-Pad166)") (class "Default")
      (node (ref "U$1") (pin "166") (pinfunction "166_166") (pintype "bidirectional"))
    )
    (net (code "162") (name "unconnected-(U$1-Pad167)") (class "Default")
      (node (ref "U$1") (pin "167") (pinfunction "167_167") (pintype "bidirectional"))
    )
    (net (code "163") (name "unconnected-(U$1-Pad168)") (class "Default")
      (node (ref "U$1") (pin "168") (pinfunction "168_168") (pintype "bidirectional"))
    )
    (net (code "164") (name "unconnected-(U$1-Pad173)") (class "Default")
      (node (ref "U$1") (pin "173") (pinfunction "173_173") (pintype "bidirectional"))
    )
    (net (code "165") (name "unconnected-(U$1-Pad176)") (class "Default")
      (node (ref "U$1") (pin "176") (pinfunction "176_176") (pintype "bidirectional"))
    )
    (net (code "166") (name "unconnected-(U$1-Pad177)") (class "Default")
      (node (ref "U$1") (pin "177") (pinfunction "177_177") (pintype "bidirectional"))
    )
    (net (code "167") (name "unconnected-(U$1-Pad178)") (class "Default")
      (node (ref "U$1") (pin "178") (pinfunction "178_178") (pintype "bidirectional"))
    )
    (net (code "168") (name "unconnected-(U$1-Pad180)") (class "Default")
      (node (ref "U$1") (pin "180") (pinfunction "180_180") (pintype "bidirectional"))
    )
    (net (code "169") (name "unconnected-(U$1-Pad181)") (class "Default")
      (node (ref "U$1") (pin "181") (pinfunction "181_181") (pintype "bidirectional"))
    )
    (net (code "170") (name "unconnected-(U$1-Pad182)") (class "Default")
      (node (ref "U$1") (pin "182") (pinfunction "182_182") (pintype "bidirectional"))
    )
    (net (code "171") (name "unconnected-(U$1-Pad186)") (class "Default")
      (node (ref "U$1") (pin "186") (pinfunction "186_186") (pintype "bidirectional"))
    )
    (net (code "172") (name "unconnected-(U$1-Pad187)") (class "Default")
      (node (ref "U$1") (pin "187") (pinfunction "187_187") (pintype "bidirectional"))
    )
    (net (code "173") (name "unconnected-(U$1-Pad188)") (class "Default")
      (node (ref "U$1") (pin "188") (pinfunction "188_188") (pintype "bidirectional"))
    )
    (net (code "174") (name "unconnected-(U$1-Pad189)") (class "Default")
      (node (ref "U$1") (pin "189") (pinfunction "189_189") (pintype "bidirectional"))
    )
    (net (code "175") (name "unconnected-(U$1-Pad190)") (class "Default")
      (node (ref "U$1") (pin "190") (pinfunction "190_190") (pintype "bidirectional"))
    )
    (net (code "176") (name "unconnected-(U$1-Pad191)") (class "Default")
      (node (ref "U$1") (pin "191") (pinfunction "191_191") (pintype "bidirectional"))
    )
    (net (code "177") (name "unconnected-(U$1-Pad192)") (class "Default")
      (node (ref "U$1") (pin "192") (pinfunction "192_192") (pintype "bidirectional"))
    )
    (net (code "178") (name "unconnected-(U$1-Pad193)") (class "Default")
      (node (ref "U$1") (pin "193") (pinfunction "193_193") (pintype "bidirectional"))
    )
    (net (code "179") (name "unconnected-(U$1-Pad194)") (class "Default")
      (node (ref "U$1") (pin "194") (pinfunction "194_194") (pintype "bidirectional"))
    )
    (net (code "180") (name "unconnected-(U$1-Pad199)") (class "Default")
      (node (ref "U$1") (pin "199") (pinfunction "199_199") (pintype "bidirectional"))
    )
    (net (code "181") (name "unconnected-(U$1-Pad202)") (class "Default")
      (node (ref "U$1") (pin "202") (pinfunction "202_202") (pintype "bidirectional"))
    )
    (net (code "182") (name "unconnected-(U$1-Pad203)") (class "Default")
      (node (ref "U$1") (pin "203") (pinfunction "203_203") (pintype "bidirectional"))
    )
    (net (code "183") (name "unconnected-(U$1-Pad204)") (class "Default")
      (node (ref "U$1") (pin "204") (pinfunction "204_204") (pintype "bidirectional"))
    )
    (net (code "184") (name "unconnected-(U$1-Pad206)") (class "Default")
      (node (ref "U$1") (pin "206") (pinfunction "206_206") (pintype "bidirectional"))
    )
    (net (code "185") (name "unconnected-(U$1-Pad207)") (class "Default")
      (node (ref "U$1") (pin "207") (pinfunction "207_207") (pintype "bidirectional"))
    )
    (net (code "186") (name "unconnected-(U$1-Pad208)") (class "Default")
      (node (ref "U$1") (pin "208") (pinfunction "208_208") (pintype "bidirectional"))
    )
    (net (code "187") (name "unconnected-(U1-PB2(SS{slash}OC1B)-Pad16)") (class "Default")
      (node (ref "U1") (pin "16") (pinfunction "PB2(SS/OC1B)_16") (pintype "bidirectional"))
    )
    (net (code "188") (name "unconnected-(U1-PC0(ADC0)-Pad23)") (class "Default")
      (node (ref "U1") (pin "23") (pinfunction "PC0(ADC0)_23") (pintype "bidirectional"))
    )
    (net (code "189") (name "unconnected-(U1-PC1(ADC1)-Pad24)") (class "Default")
      (node (ref "U1") (pin "24") (pinfunction "PC1(ADC1)_24") (pintype "bidirectional"))
    )
    (net (code "190") (name "unconnected-(U1-PC2(ADC2)-Pad25)") (class "Default")
      (node (ref "U1") (pin "25") (pinfunction "PC2(ADC2)_25") (pintype "bidirectional"))
    )
    (net (code "191") (name "unconnected-(U1-PC3(ADC3)-Pad26)") (class "Default")
      (node (ref "U1") (pin "26") (pinfunction "PC3(ADC3)_26") (pintype "bidirectional"))
    )
    (net (code "192") (name "unconnected-(U1-PC4(ADC4{slash}SDA)-Pad27)") (class "Default")
      (node (ref "U1") (pin "27") (pinfunction "PC4(ADC4/SDA)_27") (pintype "bidirectional"))
    )
    (net (code "193") (name "unconnected-(U1-PC5(ADC5{slash}SCL)-Pad28)") (class "Default")
      (node (ref "U1") (pin "28") (pinfunction "PC5(ADC5/SCL)_28") (pintype "bidirectional"))
    )
  )
)
